# power_supply.net
KiCad netlist of a schematic drawn in Altium Designer
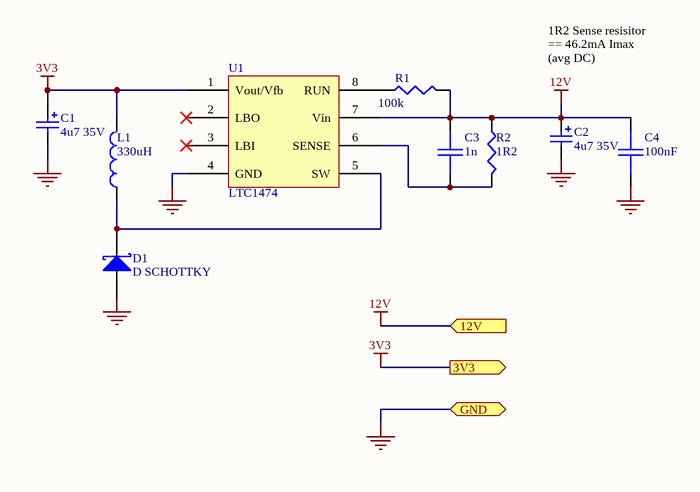
[diagram p0: power_supply.SchDoc]

(export (version "E")
  (design (tool "Eeschema 10.0.6"))
  (components
    (comp (ref "C1")
      (value "4u7 35V")
      (footprint "MCCT-CASEC")
      (description "Polarized Capacitor (Surface Mount)")
      (libsource (lib "Miscellaneous Devices") (part "Cap Pol3"))
    )
    (comp (ref "C2")
      (value "4u7 35V")
      (footprint "MCCT-CASEC")
      (description "Polarized Capacitor (Surface Mount)")
      (libsource (lib "Miscellaneous Devices") (part "Cap Pol3"))
    )
    (comp (ref "C3")
      (value "1n")
      (footprint "0603")
      (description "Capacitor")
      (libsource (lib "Miscellaneous Devices") (part "CAP"))
    )
    (comp (ref "C4")
      (value "100nF")
      (footprint "0603")
      (description "Capacitor")
      (libsource (lib "Miscellaneous Devices") (part "CAP"))
    )
    (comp (ref "D1")
      (value "D SCHOTTKY")
      (footprint "SMB")
      (description "Schottky Diode")
      (fields (field (name "MANUFACTURER") "Generic Components") (field (name "PUBLISHER") "Altium Limited"))
      (libsource (lib "RCLDQ") (part "D SCHOTTKY"))
    )
    (comp (ref "L1")
      (value "330uH")
      (footprint "1812")
      (description "Inductor")
      (libsource (lib "Miscellaneous Devices") (part "Inductor"))
    )
    (comp (ref "R1")
      (value "100k")
      (footprint "0603")
      (description "Resistor")
      (libsource (lib "RCLDQ") (part "RES1"))
    )
    (comp (ref "R2")
      (value "1R2")
      (footprint "0603")
      (description "Resistor")
      (libsource (lib "Miscellaneous Devices") (part "RES1"))
    )
    (comp (ref "U1")
      (value "LTC1474")
      (footprint "SO8")
      (description "Step-down converter")
      (libsource (lib "MiscellaneousIC") (part "LTC1474"))
    )
  )
  (nets
    (net (code "1") (name "3V3") (class "Default")
      (node (ref "C1") (pin "1") (pinfunction "1_1") (pintype "passive"))
      (node (ref "L1") (pin "2") (pinfunction "2_2") (pintype "passive"))
      (node (ref "U1") (pin "1") (pinfunction "Vout/Vfb_1") (pintype "passive"))
    )
    (net (code "2") (name "12V") (class "Default")
      (node (ref "C2") (pin "1") (pinfunction "1_1") (pintype "passive"))
      (node (ref "C3") (pin "1") (pinfunction "1_1") (pintype "passive"))
      (node (ref "C4") (pin "1") (pinfunction "1_1") (pintype "passive"))
      (node (ref "R1") (pin "2") (pinfunction "2_2") (pintype "passive"))
      (node (ref "R2") (pin "1") (pinfunction "1_1") (pintype "passive"))
      (node (ref "U1") (pin "7") (pinfunction "Vin_7") (pintype "passive"))
    )
    (net (code "3") (name "GND") (class "Default")
      (node (ref "C1") (pin "2") (pinfunction "2_2") (pintype "passive"))
      (node (ref "C2") (pin "2") (pinfunction "2_2") (pintype "passive"))
      (node (ref "C4") (pin "2") (pinfunction "2_2") (pintype "passive"))
      (node (ref "D1") (pin "A") (pinfunction "A_A") (pintype "passive"))
      (node (ref "U1") (pin "4") (pinfunction "GND_4") (pintype "passive"))
    )
    (net (code "4") (name "Net-(U1-RUN)") (class "Default")
      (node (ref "R1") (pin "1") (pinfunction "1_1") (pintype "passive"))
      (node (ref "U1") (pin "8") (pinfunction "RUN_8") (pintype "passive"))
    )
    (net (code "5") (name "Net-(U1-SENSE)") (class "Default")
      (node (ref "C3") (pin "2") (pinfunction "2_2") (pintype "passive"))
      (node (ref "R2") (pin "2") (pinfunction "2_2") (pintype "passive"))
      (node (ref "U1") (pin "6") (pinfunction "SENSE_6") (pintype "passive"))
    )
    (net (code "6") (name "Net-(U1-SW)") (class "Default")
      (node (ref "D1") (pin "K") (pinfunction "K_K") (pintype "passive"))
      (node (ref "L1") (pin "1") (pinfunction "1_1") (pintype "passive"))
      (node (ref "U1") (pin "5") (pinfunction "SW_5") (pintype "passive"))
    )
    (net (code "7") (name "unconnected-(U1-LBI-Pad3)") (class "Default")
      (node (ref "U1") (pin "3") (pinfunction "LBI_3") (pintype "passive+no_connect"))
    )
    (net (code "8") (name "unconnected-(U1-LBO-Pad2)") (class "Default")
      (node (ref "U1") (pin "2") (pinfunction "LBO_2") (pintype "passive+no_connect"))
    )
  )
)
